# Connectors.net
KiCad netlist of a schematic drawn in Altium Designer
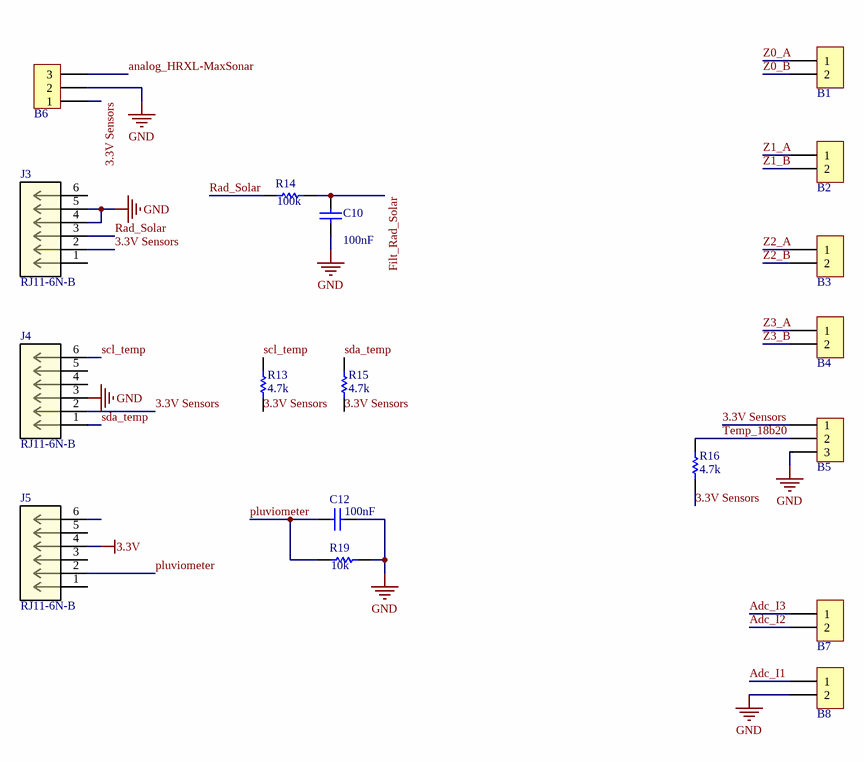
[diagram p0: Connectors.SchDoc]

(export (version "E")
  (design (tool "Eeschema 10.0.6"))
  (components
    (comp (ref "B1")
      (value "Borne")
      (footprint "BORNE2")
      (description "Terminal Atornillable 2 salidas")
      (libsource (lib "Conectores") (part "Borne2"))
    )
    (comp (ref "B2")
      (value "Borne")
      (footprint "BORNE2")
      (description "Terminal Atornillable 2 salidas")
      (libsource (lib "Conectores") (part "Borne2"))
    )
    (comp (ref "B3")
      (value "Borne")
      (footprint "BORNE2")
      (description "Terminal Atornillable 2 salidas")
      (libsource (lib "Conectores") (part "Borne2"))
    )
    (comp (ref "B4")
      (value "Borne")
      (footprint "BORNE2")
      (description "Terminal Atornillable 2 salidas")
      (libsource (lib "Conectores") (part "Borne2"))
    )
    (comp (ref "B5")
      (value "Borne 3")
      (footprint "BORNE3")
      (description "Terminal atornillable 3 salidas")
      (libsource (lib "") (part "Borne3_1"))
    )
    (comp (ref "B6")
      (value "Borne 3")
      (footprint "BORNE3")
      (description "Terminal atornillable 3 salidas")
      (libsource (lib "Conectores") (part "Borne3"))
    )
    (comp (ref "B7")
      (value "Borne")
      (footprint "BORNE2")
      (description "Terminal Atornillable 2 salidas")
      (libsource (lib "Conectores") (part "Borne2"))
    )
    (comp (ref "B8")
      (value "Borne")
      (footprint "BORNE2")
      (description "Terminal Atornillable 2 salidas")
      (libsource (lib "Conectores") (part "Borne2"))
    )
    (comp (ref "C10")
      (value "100nF")
      (footprint "CAP_X7R_0805_AVX")
      (description "Capacitor ceramico")
      (libsource (lib "Capacitores") (part "Capacitor ceramico"))
    )
    (comp (ref "C12")
      (value "100nF")
      (footprint "CAP_X7R_0805_AVX")
      (description "Capacitor ceramico")
      (libsource (lib "Capacitores") (part "Capacitor ceramico"))
    )
    (comp (ref "J3")
      (value "RJ11-6N-B")
      (footprint "CONN_RJ11-6N-B_TEC")
      (description "No Description Available")
      (fields (field (name "COPYRIGHT") "Copyright (C) 2018 Accelerated Designs. All rights reserved"))
      (libsource (lib "2021-03-05_21-31-22") (part "RJ11-6N-B"))
    )
    (comp (ref "J4")
      (value "RJ11-6N-B")
      (footprint "CONN_RJ11-6N-B_TEC")
      (description "No Description Available")
      (fields (field (name "COPYRIGHT") "Copyright (C) 2018 Accelerated Designs. All rights reserved"))
      (libsource (lib "2021-03-05_21-31-22") (part "RJ11-6N-B"))
    )
    (comp (ref "J5")
      (value "RJ11-6N-B")
      (footprint "CONN_RJ11-6N-B_TEC")
      (description "No Description Available")
      (fields (field (name "COPYRIGHT") "Copyright (C) 2018 Accelerated Designs. All rights reserved"))
      (libsource (lib "2021-03-05_21-31-22") (part "RJ11-6N-B"))
    )
    (comp (ref "R13")
      (value "4.7k")
      (footprint "6-0805_N")
      (description "Resistor empaque ceramico axial de 1/4 de watt")
      (fields (field (name "Comment") "Res") (field (name "PUBLISHER") "Altium Limited"))
      (libsource (lib "Resistencias de carbon") (part "Resistor 1/4 watt"))
    )
    (comp (ref "R14")
      (value "100k")
      (footprint "6-0805_N")
      (description "Resistor empaque ceramico axial de 1/4 de watt")
      (fields (field (name "Comment") "Res") (field (name "PUBLISHER") "Altium Limited"))
      (libsource (lib "Resistencias de carbon") (part "Resistor 1/4 watt"))
    )
    (comp (ref "R15")
      (value "4.7k")
      (footprint "6-0805_N")
      (description "Resistor empaque ceramico axial de 1/4 de watt")
      (fields (field (name "Comment") "Res") (field (name "PUBLISHER") "Altium Limited"))
      (libsource (lib "Resistencias de carbon") (part "Resistor 1/4 watt"))
    )
    (comp (ref "R16")
      (value "4.7k")
      (footprint "6-0805_N")
      (description "Resistor empaque ceramico axial de 1/4 de watt")
      (fields (field (name "Comment") "Res") (field (name "PUBLISHER") "Altium Limited"))
      (libsource (lib "Resistencias de carbon") (part "Resistor 1/4 watt"))
    )
    (comp (ref "R19")
      (value "10k")
      (footprint "6-0805_N")
      (description "Resistor empaque ceramico axial de 1/4 de watt")
      (fields (field (name "Comment") "Res") (field (name "PUBLISHER") "Altium Limited"))
      (libsource (lib "Resistencias de carbon") (part "Resistor 1/4 watt"))
    )
  )
  (nets
    (net (code "1") (name "/3.3V Sensors") (class "Default")
      (node (ref "B5") (pin "1") (pinfunction "1_1") (pintype "passive"))
      (node (ref "B6") (pin "1") (pinfunction "1_1") (pintype "passive"))
      (node (ref "J3") (pin "2") (pinfunction "2_2") (pintype "passive"))
      (node (ref "J4") (pin "2") (pinfunction "2_2") (pintype "passive"))
      (node (ref "R13") (pin "1") (pinfunction "1_1") (pintype "passive"))
      (node (ref "R15") (pin "1") (pinfunction "1_1") (pintype "passive"))
      (node (ref "R16") (pin "1") (pinfunction "1_1") (pintype "passive"))
    )
    (net (code "2") (name "/Adc_I1") (class "Default")
      (node (ref "B8") (pin "1") (pinfunction "1_1") (pintype "passive"))
    )
    (net (code "3") (name "/Adc_I2") (class "Default")
      (node (ref "B7") (pin "2") (pinfunction "2_2") (pintype "passive"))
    )
    (net (code "4") (name "/Adc_I3") (class "Default")
      (node (ref "B7") (pin "1") (pinfunction "1_1") (pintype "passive"))
    )
    (net (code "5") (name "/Filt_Rad_Solar") (class "Default")
      (node (ref "C10") (pin "1") (pinfunction "1_1") (pintype "passive"))
      (node (ref "R14") (pin "2") (pinfunction "2_2") (pintype "passive"))
    )
    (net (code "6") (name "/Rad_Solar") (class "Default")
      (node (ref "J3") (pin "3") (pinfunction "3_3") (pintype "passive"))
      (node (ref "R14") (pin "1") (pinfunction "1_1") (pintype "passive"))
    )
    (net (code "7") (name "/Temp_18b20") (class "Default")
      (node (ref "B5") (pin "2") (pinfunction "2_2") (pintype "passive"))
      (node (ref "R16") (pin "2") (pinfunction "2_2") (pintype "passive"))
    )
    (net (code "8") (name "/Z0_A") (class "Default")
      (node (ref "B1") (pin "1") (pinfunction "1_1") (pintype "passive"))
    )
    (net (code "9") (name "/Z0_B") (class "Default")
      (node (ref "B1") (pin "2") (pinfunction "2_2") (pintype "passive"))
    )
    (net (code "10") (name "/Z1_A") (class "Default")
      (node (ref "B2") (pin "1") (pinfunction "1_1") (pintype "passive"))
    )
    (net (code "11") (name "/Z1_B") (class "Default")
      (node (ref "B2") (pin "2") (pinfunction "2_2") (pintype "passive"))
    )
    (net (code "12") (name "/Z2_A") (class "Default")
      (node (ref "B3") (pin "1") (pinfunction "1_1") (pintype "passive"))
    )
    (net (code "13") (name "/Z2_B") (class "Default")
      (node (ref "B3") (pin "2") (pinfunction "2_2") (pintype "passive"))
    )
    (net (code "14") (name "/Z3_A") (class "Default")
      (node (ref "B4") (pin "1") (pinfunction "1_1") (pintype "passive"))
    )
    (net (code "15") (name "/Z3_B") (class "Default")
      (node (ref "B4") (pin "2") (pinfunction "2_2") (pintype "passive"))
    )
    (net (code "16") (name "/analog_HRXL-MaxSonar") (class "Default")
      (node (ref "B6") (pin "3") (pinfunction "3_3") (pintype "passive"))
    )
    (net (code "17") (name "/pluviometer") (class "Default")
      (node (ref "C12") (pin "2") (pinfunction "2_2") (pintype "passive"))
      (node (ref "J5") (pin "2") (pinfunction "2_2") (pintype "passive"))
      (node (ref "R19") (pin "1") (pinfunction "1_1") (pintype "passive"))
    )
    (net (code "18") (name "/scl_temp") (class "Default")
      (node (ref "J4") (pin "6") (pinfunction "6_6") (pintype "passive"))
      (node (ref "R13") (pin "2") (pinfunction "2_2") (pintype "passive"))
    )
    (net (code "19") (name "/sda_temp") (class "Default")
      (node (ref "J4") (pin "1") (pinfunction "1_1") (pintype "passive"))
      (node (ref "R15") (pin "2") (pinfunction "2_2") (pintype "passive"))
    )
    (net (code "20") (name "3.3V") (class "Default")
      (node (ref "J5") (pin "4") (pinfunction "4_4") (pintype "passive"))
    )
    (net (code "21") (name "GND") (class "Default")
      (node (ref "B5") (pin "3") (pinfunction "3_3") (pintype "passive"))
      (node (ref "B6") (pin "2") (pinfunction "2_2") (pintype "passive"))
      (node (ref "B8") (pin "2") (pinfunction "2_2") (pintype "passive"))
      (node (ref "C10") (pin "2") (pinfunction "2_2") (pintype "passive"))
      (node (ref "C12") (pin "1") (pinfunction "1_1") (pintype "passive"))
      (node (ref "J3") (pin "4") (pinfunction "4_4") (pintype "passive"))
      (node (ref "J3") (pin "5") (pinfunction "5_5") (pintype "passive"))
      (node (ref "J4") (pin "3") (pinfunction "3_3") (pintype "passive"))
      (node (ref "R19") (pin "2") (pinfunction "2_2") (pintype "passive"))
    )
    (net (code "22") (name "unconnected-(J3-Pad1)") (class "Default")
      (node (ref "J3") (pin "1") (pinfunction "1_1") (pintype "passive"))
    )
    (net (code "23") (name "unconnected-(J3-Pad6)") (class "Default")
      (node (ref "J3") (pin "6") (pinfunction "6_6") (pintype "passive"))
    )
    (net (code "24") (name "unconnected-(J4-Pad4)") (class "Default")
      (node (ref "J4") (pin "4") (pinfunction "4_4") (pintype "passive"))
    )
    (net (code "25") (name "unconnected-(J4-Pad5)") (class "Default")
      (node (ref "J4") (pin "5") (pinfunction "5_5") (pintype "passive"))
    )
    (net (code "26") (name "unconnected-(J5-Pad1)") (class "Default")
      (node (ref "J5") (pin "1") (pinfunction "1_1") (pintype "passive"))
    )
    (net (code "27") (name "unconnected-(J5-Pad3)") (class "Default")
      (node (ref "J5") (pin "3") (pinfunction "3_3") (pintype "passive"))
    )
    (net (code "28") (name "unconnected-(J5-Pad5)") (class "Default")
      (node (ref "J5") (pin "5") (pinfunction "5_5") (pintype "passive"))
    )
    (net (code "29") (name "unconnected-(J5-Pad6)") (class "Default")
      (node (ref "J5") (pin "6") (pinfunction "6_6") (pintype "passive"))
    )
  )
)
